# mic2.net
KiCad netlist of a schematic drawn in EAGLE
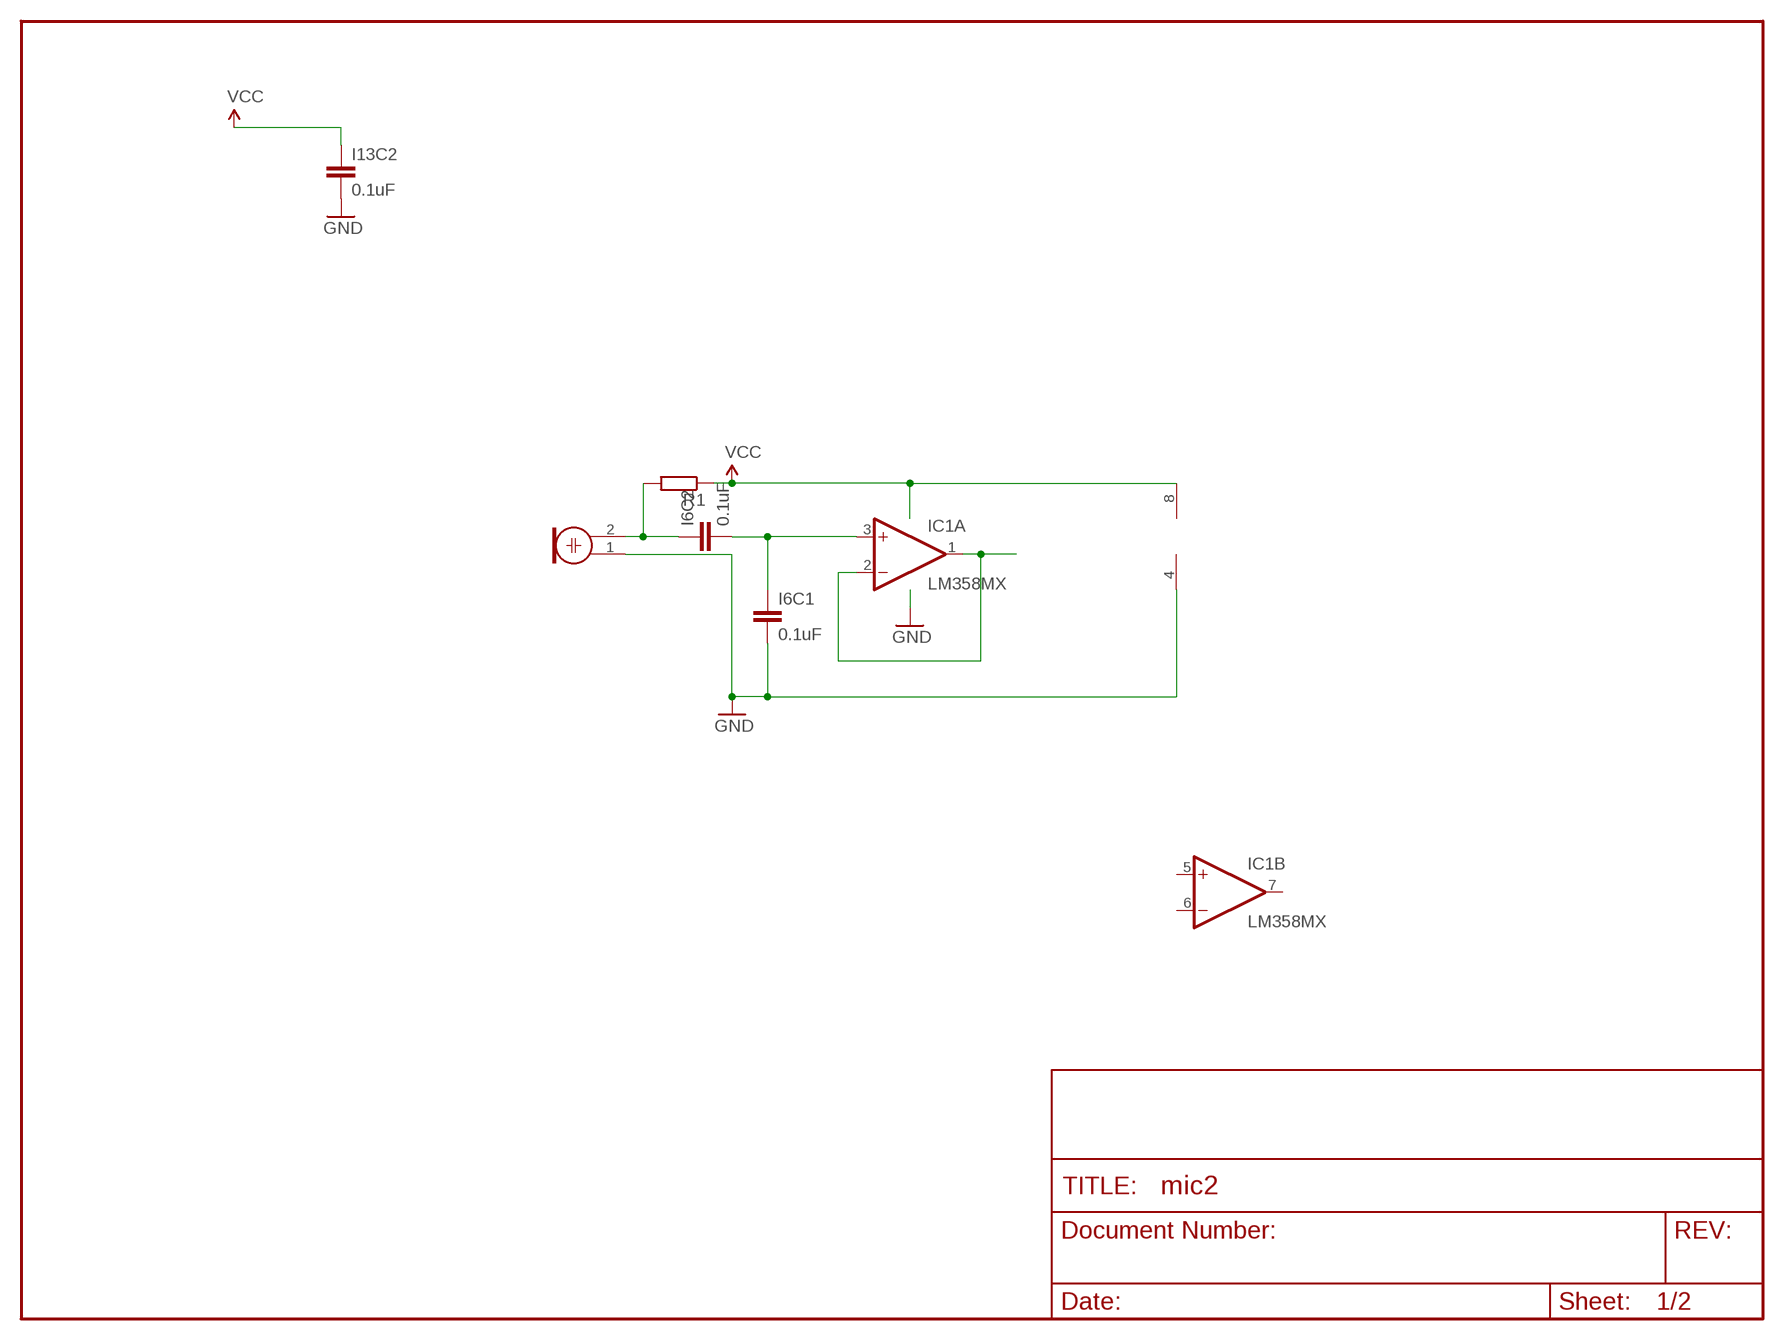
[diagram p0: schematic, sheet 1]
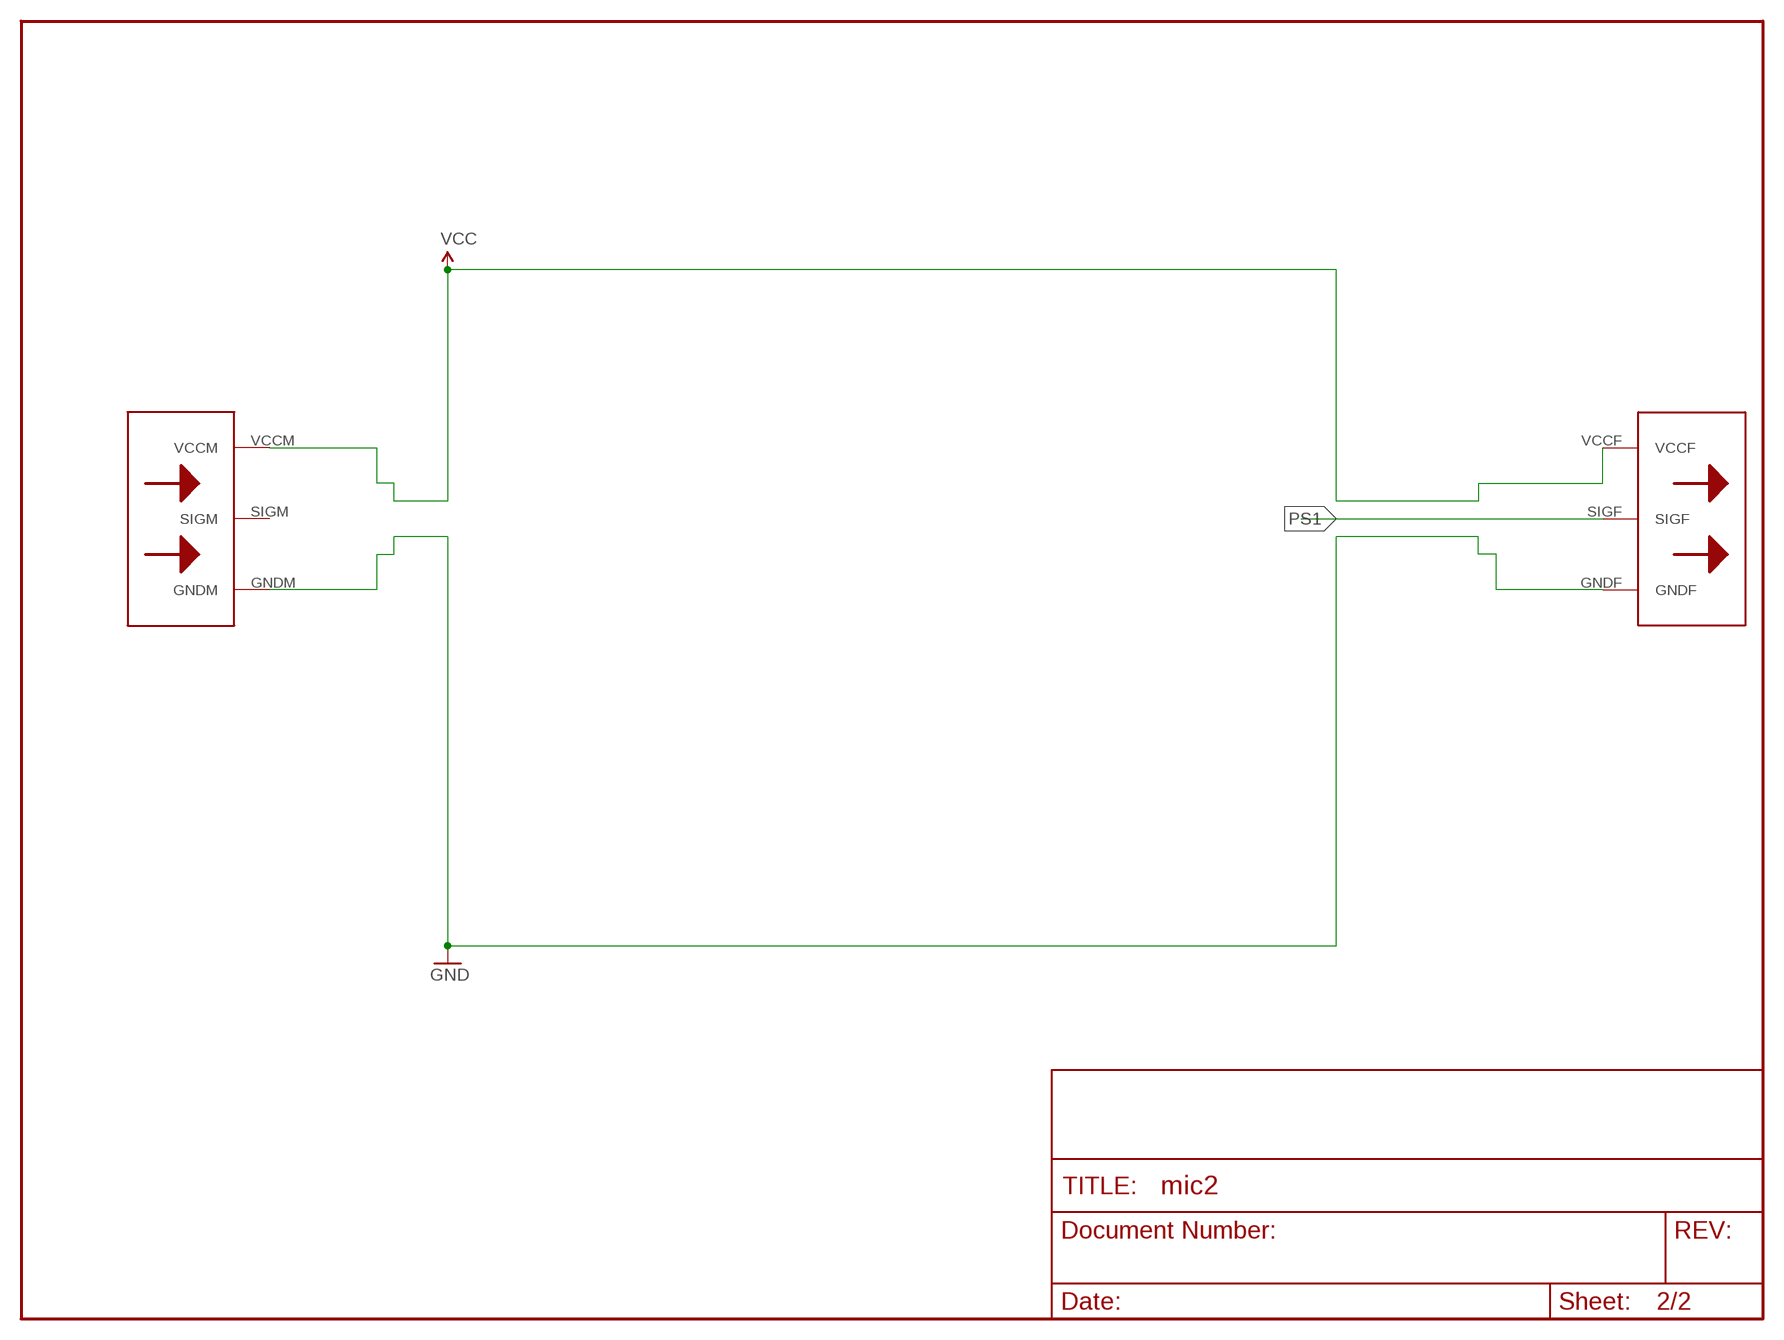
[diagram p1: schematic, sheet 2]

(export (version "E")
  (design (tool "Eeschema 10.0.6"))
  (components
    (comp (ref "I6C1")
      (value "0.1uF")
      (footprint "eagle-import:1206")
      (libsource (lib "eagle-import") (part "CAP1206"))
    )
    (comp (ref "I6C2")
      (value "0.1uF")
      (footprint "eagle-import:1206")
      (libsource (lib "eagle-import") (part "CAP1206"))
    )
    (comp (ref "I13C2")
      (value "0.1uF")
      (footprint "eagle-import:1206")
      (libsource (lib "eagle-import") (part "CAP1206"))
    )
    (comp (ref "IC1")
      (value "LM358MX")
      (footprint "eagle-import:SO08")
      (libsource (lib "eagle-import") (part "LM358MX"))
    )
    (comp (ref "M1")
      (value "ELECTRET_MICROPHON-WM-61A")
      (footprint "eagle-import:WM-61A")
      (libsource (lib "eagle-import") (part "ELECTRET_MICROPHON-WM-61A"))
    )
    (comp (ref "R1")
      (value "R-EU_M0805")
      (footprint "eagle-import:M0805")
      (libsource (lib "eagle-import") (part "R-EU_M0805"))
    )
    (comp (ref "U$3")
      (value "BIGBIT")
      (footprint "eagle-import:BIGBIT")
      (libsource (lib "eagle-import") (part "BIGBIT"))
    )
  )
  (nets
    (net (code "1") (name "GND") (class "Default")
      (node (ref "I13C2") (pin "2") (pinfunction "2_2") (pintype "passive"))
      (node (ref "I6C1") (pin "2") (pinfunction "2_2") (pintype "passive"))
      (node (ref "IC1") (pin "4") (pinfunction "V-_4") (pintype "power_in"))
      (node (ref "M1") (pin "1") (pinfunction "1_1") (pintype "passive"))
      (node (ref "U$3") (pin "GNDF") (pinfunction "GNDF_GNDF") (pintype "bidirectional"))
      (node (ref "U$3") (pin "GNDM") (pinfunction "GNDM_GNDM") (pintype "bidirectional"))
    )
    (net (code "2") (name "Net-(I6C2-Pad1)") (class "Default")
      (node (ref "I6C2") (pin "1") (pinfunction "1_1") (pintype "passive"))
      (node (ref "M1") (pin "2") (pinfunction "2_2") (pintype "passive"))
      (node (ref "R1") (pin "2") (pinfunction "2_2") (pintype "passive"))
    )
    (net (code "3") (name "Net-(IC1A-+IN)") (class "Default")
      (node (ref "I6C1") (pin "1") (pinfunction "1_1") (pintype "passive"))
      (node (ref "I6C2") (pin "2") (pinfunction "2_2") (pintype "passive"))
      (node (ref "IC1") (pin "3") (pinfunction "+IN_3") (pintype "input"))
    )
    (net (code "4") (name "Net-(IC1A--IN)") (class "Default")
      (node (ref "IC1") (pin "1") (pinfunction "OUT_1") (pintype "output"))
      (node (ref "IC1") (pin "2") (pinfunction "-IN_2") (pintype "input"))
    )
    (net (code "5") (name "PS1") (class "Default")
      (node (ref "U$3") (pin "SIGF") (pinfunction "SIGF_SIGF") (pintype "bidirectional"))
    )
    (net (code "6") (name "VCC") (class "Default")
      (node (ref "I13C2") (pin "1") (pinfunction "1_1") (pintype "passive"))
      (node (ref "IC1") (pin "8") (pinfunction "V+_8") (pintype "power_in"))
      (node (ref "R1") (pin "1") (pinfunction "1_1") (pintype "passive"))
      (node (ref "U$3") (pin "VCCF") (pinfunction "VCCF_VCCF") (pintype "bidirectional"))
      (node (ref "U$3") (pin "VCCM") (pinfunction "VCCM_VCCM") (pintype "bidirectional"))
    )
    (net (code "7") (name "unconnected-(IC1B-+IN-Pad5)") (class "Default")
      (node (ref "IC1") (pin "5") (pinfunction "+IN_5") (pintype "input"))
    )
    (net (code "8") (name "unconnected-(IC1B--IN-Pad6)") (class "Default")
      (node (ref "IC1") (pin "6") (pinfunction "-IN_6") (pintype "input"))
    )
    (net (code "9") (name "unconnected-(IC1B-OUT-Pad7)") (class "Default")
      (node (ref "IC1") (pin "7") (pinfunction "OUT_7") (pintype "output"))
    )
    (net (code "10") (name "unconnected-(U$3-PadSIGM)") (class "Default")
      (node (ref "U$3") (pin "SIGM") (pinfunction "SIGM_SIGM") (pintype "bidirectional"))
    )
  )
)
